# HoneyCar.net
KiCad netlist of a schematic drawn in EAGLE
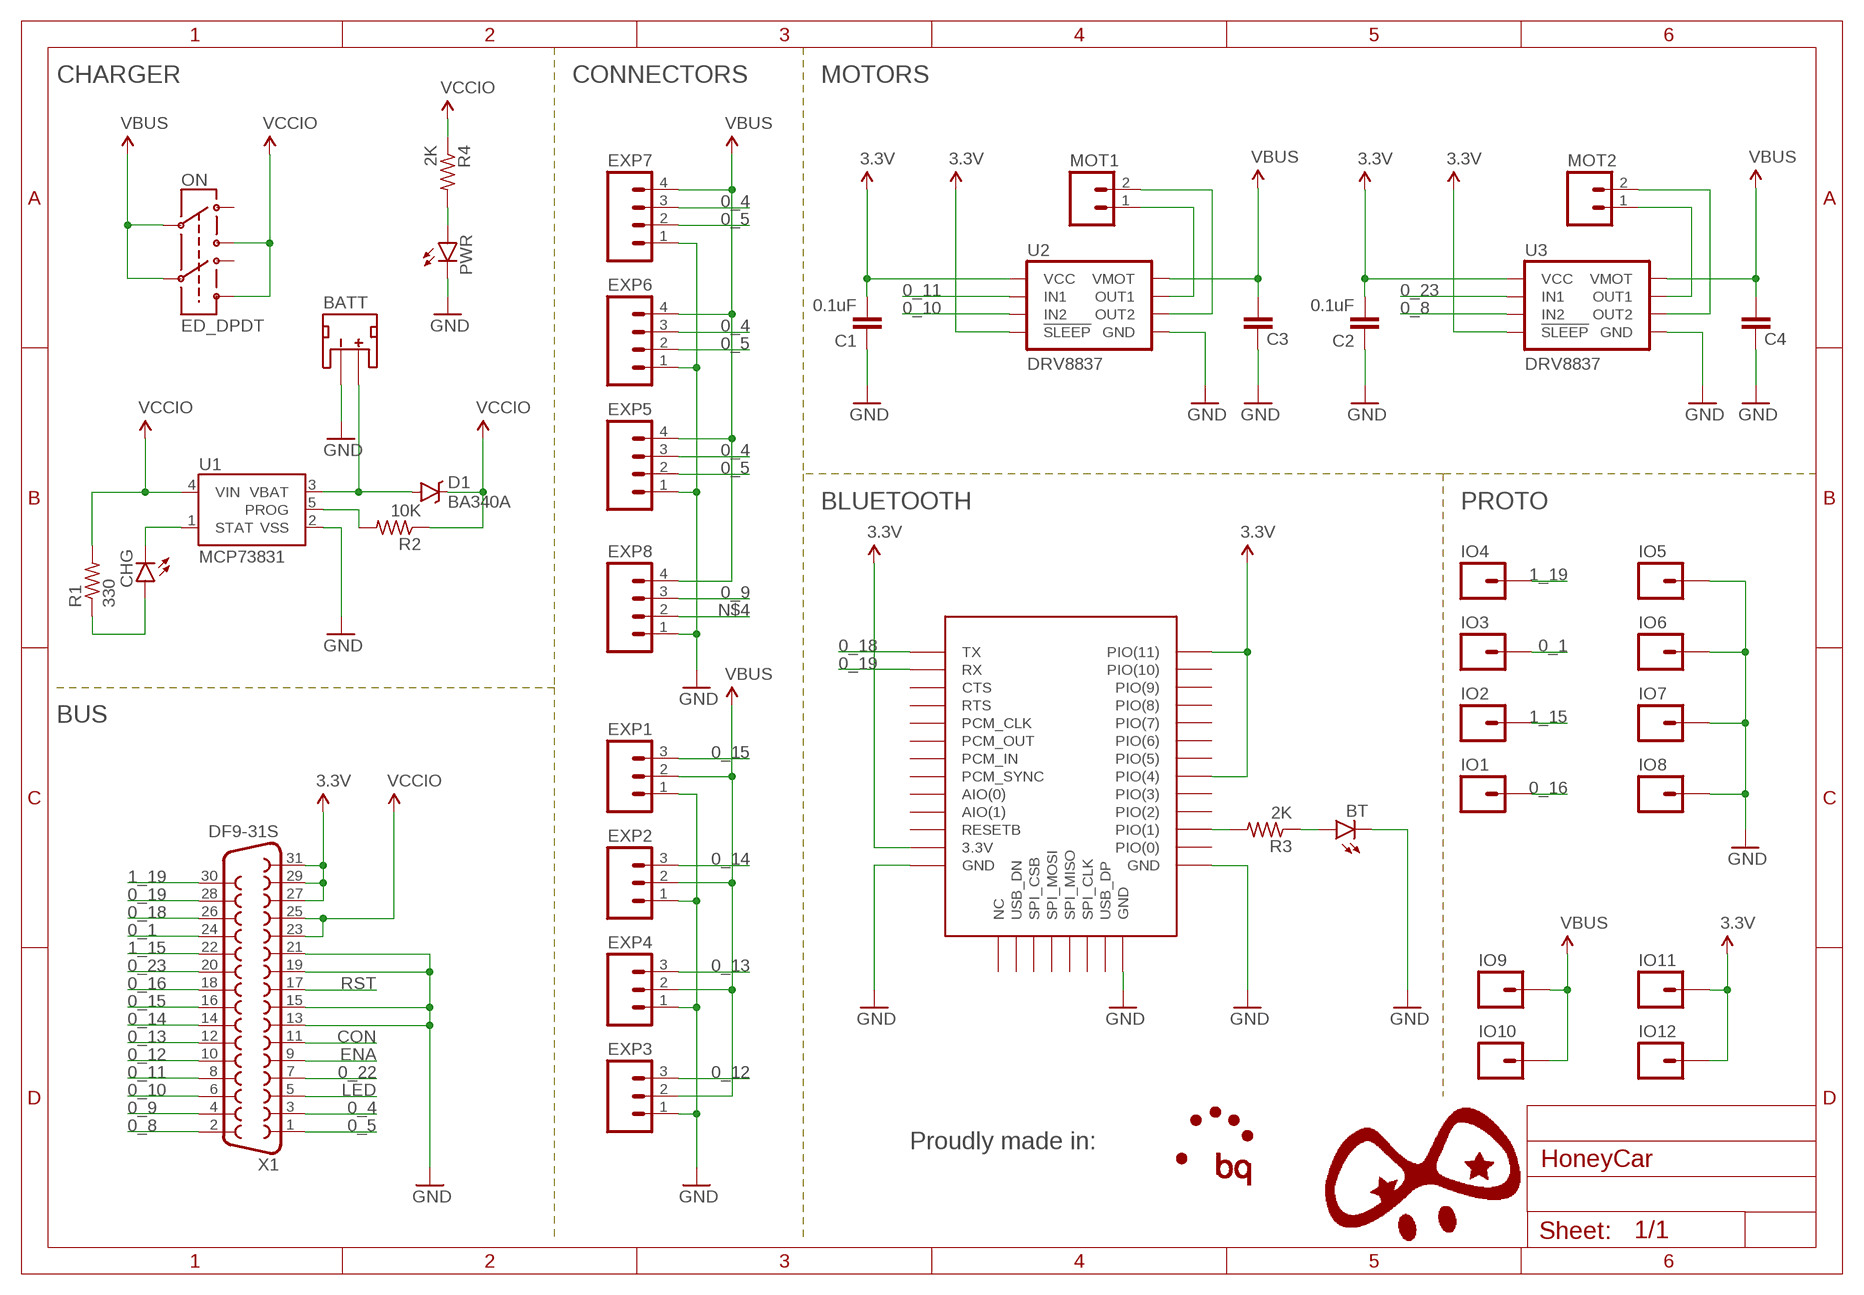
[diagram p0: schematic, sheet 1]

(export (version "E")
  (design (tool "Eeschema 10.0.6"))
  (components
    (comp (ref "BATT")
      (value "JST_2MM_MALE")
      (footprint "eagle-import:JST-2-SMD")
      (libsource (lib "eagle-import") (part "JST_2MM_MALE"))
    )
    (comp (ref "BT")
      (value "LED0603")
      (footprint "eagle-import:LED-0603")
      (libsource (lib "eagle-import") (part "LED0603"))
    )
    (comp (ref "C1")
      (value "0.1uF")
      (footprint "eagle-import:0603-CAP")
      (libsource (lib "eagle-import") (part "CAP0603-CAP"))
    )
    (comp (ref "C2")
      (value "0.1uF")
      (footprint "eagle-import:0603-CAP")
      (libsource (lib "eagle-import") (part "CAP0603-CAP"))
    )
    (comp (ref "C3")
      (value "0.1uF")
      (footprint "eagle-import:0603-CAP")
      (libsource (lib "eagle-import") (part "CAP0603-CAP"))
    )
    (comp (ref "C4")
      (value "0.1uF")
      (footprint "eagle-import:0603-CAP")
      (libsource (lib "eagle-import") (part "CAP0603-CAP"))
    )
    (comp (ref "CHG")
      (value "LED0603")
      (footprint "eagle-import:LED-0603")
      (libsource (lib "eagle-import") (part "LED0603"))
    )
    (comp (ref "D1")
      (value "BA340A")
      (footprint "eagle-import:SMA-DIODE")
      (libsource (lib "eagle-import") (part "B340A"))
    )
    (comp (ref "EXP1")
      (value "M03LOCK")
      (footprint "eagle-import:1X03_LOCK")
      (libsource (lib "eagle-import") (part "M03LOCK"))
    )
    (comp (ref "EXP2")
      (value "M03LOCK")
      (footprint "eagle-import:1X03_LOCK")
      (libsource (lib "eagle-import") (part "M03LOCK"))
    )
    (comp (ref "EXP3")
      (value "M03LOCK")
      (footprint "eagle-import:1X03_LOCK")
      (libsource (lib "eagle-import") (part "M03LOCK"))
    )
    (comp (ref "EXP4")
      (value "M03LOCK")
      (footprint "eagle-import:1X03_LOCK")
      (libsource (lib "eagle-import") (part "M03LOCK"))
    )
    (comp (ref "EXP5")
      (value "M04JST")
      (footprint "eagle-import:1X04-1.5MM_JST")
      (libsource (lib "eagle-import") (part "M04JST"))
    )
    (comp (ref "EXP6")
      (value "M04JST")
      (footprint "eagle-import:1X04-1.5MM_JST")
      (libsource (lib "eagle-import") (part "M04JST"))
    )
    (comp (ref "EXP7")
      (value "M04JST")
      (footprint "eagle-import:1X04-1.5MM_JST")
      (libsource (lib "eagle-import") (part "M04JST"))
    )
    (comp (ref "EXP8")
      (value "M04JST")
      (footprint "eagle-import:1X04-1.5MM_JST")
      (libsource (lib "eagle-import") (part "M04JST"))
    )
    (comp (ref "IC1")
      (value "BC04_BLUETOOTH")
      (footprint "eagle-import:BC04")
      (libsource (lib "eagle-import") (part "BC04_BLUETOOTH"))
    )
    (comp (ref "IO1")
      (value "M01PTH_LONGPAD")
      (footprint "eagle-import:1X01_LONGPAD")
      (libsource (lib "eagle-import") (part "M01PTH_LONGPAD"))
    )
    (comp (ref "IO2")
      (value "M01PTH_LONGPAD")
      (footprint "eagle-import:1X01_LONGPAD")
      (libsource (lib "eagle-import") (part "M01PTH_LONGPAD"))
    )
    (comp (ref "IO3")
      (value "M01PTH_LONGPAD")
      (footprint "eagle-import:1X01_LONGPAD")
      (libsource (lib "eagle-import") (part "M01PTH_LONGPAD"))
    )
    (comp (ref "IO4")
      (value "M01PTH_LONGPAD")
      (footprint "eagle-import:1X01_LONGPAD")
      (libsource (lib "eagle-import") (part "M01PTH_LONGPAD"))
    )
    (comp (ref "IO5")
      (value "M01PTH_LONGPAD")
      (footprint "eagle-import:1X01_LONGPAD")
      (libsource (lib "eagle-import") (part "M01PTH_LONGPAD"))
    )
    (comp (ref "IO6")
      (value "M01PTH_LONGPAD")
      (footprint "eagle-import:1X01_LONGPAD")
      (libsource (lib "eagle-import") (part "M01PTH_LONGPAD"))
    )
    (comp (ref "IO7")
      (value "M01PTH_LONGPAD")
      (footprint "eagle-import:1X01_LONGPAD")
      (libsource (lib "eagle-import") (part "M01PTH_LONGPAD"))
    )
    (comp (ref "IO8")
      (value "M01PTH_LONGPAD")
      (footprint "eagle-import:1X01_LONGPAD")
      (libsource (lib "eagle-import") (part "M01PTH_LONGPAD"))
    )
    (comp (ref "IO9")
      (value "M01PTH_LONGPAD")
      (footprint "eagle-import:1X01_LONGPAD")
      (libsource (lib "eagle-import") (part "M01PTH_LONGPAD"))
    )
    (comp (ref "IO10")
      (value "M01PTH_LONGPAD")
      (footprint "eagle-import:1X01_LONGPAD")
      (libsource (lib "eagle-import") (part "M01PTH_LONGPAD"))
    )
    (comp (ref "IO11")
      (value "M01PTH_LONGPAD")
      (footprint "eagle-import:1X01_LONGPAD")
      (libsource (lib "eagle-import") (part "M01PTH_LONGPAD"))
    )
    (comp (ref "IO12")
      (value "M01PTH_LONGPAD")
      (footprint "eagle-import:1X01_LONGPAD")
      (libsource (lib "eagle-import") (part "M01PTH_LONGPAD"))
    )
    (comp (ref "MOT1")
      (value "M02POLAR")
      (footprint "eagle-import:MOLEX-1X2")
      (libsource (lib "eagle-import") (part "M02POLAR"))
    )
    (comp (ref "MOT2")
      (value "M02POLAR")
      (footprint "eagle-import:MOLEX-1X2")
      (libsource (lib "eagle-import") (part "M02POLAR"))
    )
    (comp (ref "ON")
      (value "ED_DPDT")
      (footprint "eagle-import:ED_DPDT")
      (libsource (lib "eagle-import") (part "ED_DPDT"))
    )
    (comp (ref "PWR")
      (value "LED0603")
      (footprint "eagle-import:LED-0603")
      (libsource (lib "eagle-import") (part "LED0603"))
    )
    (comp (ref "R1")
      (value "330")
      (footprint "eagle-import:R0402")
      (libsource (lib "eagle-import") (part "R-US_R0402"))
    )
    (comp (ref "R2")
      (value "10K")
      (footprint "eagle-import:R0402")
      (libsource (lib "eagle-import") (part "R-US_R0402"))
    )
    (comp (ref "R3")
      (value "2K")
      (footprint "eagle-import:R0402")
      (libsource (lib "eagle-import") (part "R-US_R0402"))
    )
    (comp (ref "R4")
      (value "2K")
      (footprint "eagle-import:R0402")
      (libsource (lib "eagle-import") (part "R-US_R0402"))
    )
    (comp (ref "U1")
      (value "MCP73831")
      (footprint "eagle-import:SOT23-5")
      (libsource (lib "eagle-import") (part "MCP73831"))
    )
    (comp (ref "U2")
      (value "DRV8837")
      (footprint "eagle-import:DSG")
      (libsource (lib "eagle-import") (part "DRV8837"))
    )
    (comp (ref "U3")
      (value "DRV8837")
      (footprint "eagle-import:DSG")
      (libsource (lib "eagle-import") (part "DRV8837"))
    )
    (comp (ref "X1")
      (value "DF9-31S")
      (footprint "eagle-import:DF9-31S")
      (fields (field (name "MPN") "DF9-31S-1V(32)"))
      (libsource (lib "eagle-import") (part "DF9-31S"))
    )
  )
  (nets
    (net (code "1") (name "/0_1") (class "Default")
      (node (ref "IO3") (pin "1") (pinfunction "1_1") (pintype "passive"))
      (node (ref "X1") (pin "24") (pinfunction "24_24") (pintype "passive"))
    )
    (net (code "2") (name "/0_4") (class "Default")
      (node (ref "EXP5") (pin "3") (pinfunction "3_3") (pintype "passive"))
      (node (ref "EXP6") (pin "3") (pinfunction "3_3") (pintype "passive"))
      (node (ref "EXP7") (pin "3") (pinfunction "3_3") (pintype "passive"))
      (node (ref "X1") (pin "3") (pinfunction "3_3") (pintype "passive"))
    )
    (net (code "3") (name "/0_5") (class "Default")
      (node (ref "EXP5") (pin "2") (pinfunction "2_2") (pintype "passive"))
      (node (ref "EXP6") (pin "2") (pinfunction "2_2") (pintype "passive"))
      (node (ref "EXP7") (pin "2") (pinfunction "2_2") (pintype "passive"))
      (node (ref "X1") (pin "1") (pinfunction "1_1") (pintype "passive"))
    )
    (net (code "4") (name "/0_8") (class "Default")
      (node (ref "U3") (pin "5") (pinfunction "IN2_5") (pintype "bidirectional"))
      (node (ref "X1") (pin "2") (pinfunction "2_2") (pintype "passive"))
    )
    (net (code "5") (name "/0_9") (class "Default")
      (node (ref "EXP8") (pin "3") (pinfunction "3_3") (pintype "passive"))
      (node (ref "X1") (pin "4") (pinfunction "4_4") (pintype "passive"))
    )
    (net (code "6") (name "/0_10") (class "Default")
      (node (ref "U2") (pin "5") (pinfunction "IN2_5") (pintype "bidirectional"))
      (node (ref "X1") (pin "6") (pinfunction "6_6") (pintype "passive"))
    )
    (net (code "7") (name "/0_11") (class "Default")
      (node (ref "U2") (pin "6") (pinfunction "IN1_6") (pintype "bidirectional"))
      (node (ref "X1") (pin "8") (pinfunction "8_8") (pintype "passive"))
    )
    (net (code "8") (name "/0_12") (class "Default")
      (node (ref "EXP3") (pin "3") (pinfunction "3_3") (pintype "passive"))
      (node (ref "X1") (pin "10") (pinfunction "10_10") (pintype "passive"))
    )
    (net (code "9") (name "/0_13") (class "Default")
      (node (ref "EXP4") (pin "3") (pinfunction "3_3") (pintype "passive"))
      (node (ref "X1") (pin "12") (pinfunction "12_12") (pintype "passive"))
    )
    (net (code "10") (name "/0_14") (class "Default")
      (node (ref "EXP2") (pin "3") (pinfunction "3_3") (pintype "passive"))
      (node (ref "X1") (pin "14") (pinfunction "14_14") (pintype "passive"))
    )
    (net (code "11") (name "/0_15") (class "Default")
      (node (ref "EXP1") (pin "3") (pinfunction "3_3") (pintype "passive"))
      (node (ref "X1") (pin "16") (pinfunction "16_16") (pintype "passive"))
    )
    (net (code "12") (name "/0_16") (class "Default")
      (node (ref "IO1") (pin "1") (pinfunction "1_1") (pintype "passive"))
      (node (ref "X1") (pin "18") (pinfunction "18_18") (pintype "passive"))
    )
    (net (code "13") (name "/0_18") (class "Default")
      (node (ref "IC1") (pin "P$1") (pinfunction "TX_P$1") (pintype "bidirectional"))
      (node (ref "X1") (pin "26") (pinfunction "26_26") (pintype "passive"))
    )
    (net (code "14") (name "/0_19") (class "Default")
      (node (ref "IC1") (pin "P$2") (pinfunction "RX_P$2") (pintype "bidirectional"))
      (node (ref "X1") (pin "28") (pinfunction "28_28") (pintype "passive"))
    )
    (net (code "15") (name "/0_22") (class "Default")
      (node (ref "X1") (pin "7") (pinfunction "7_7") (pintype "passive"))
    )
    (net (code "16") (name "/0_23") (class "Default")
      (node (ref "U3") (pin "6") (pinfunction "IN1_6") (pintype "bidirectional"))
      (node (ref "X1") (pin "20") (pinfunction "20_20") (pintype "passive"))
    )
    (net (code "17") (name "/1_15") (class "Default")
      (node (ref "IO2") (pin "1") (pinfunction "1_1") (pintype "passive"))
      (node (ref "X1") (pin "22") (pinfunction "22_22") (pintype "passive"))
    )
    (net (code "18") (name "/1_19") (class "Default")
      (node (ref "IO4") (pin "1") (pinfunction "1_1") (pintype "passive"))
      (node (ref "X1") (pin "30") (pinfunction "30_30") (pintype "passive"))
    )
    (net (code "19") (name "/CON") (class "Default")
      (node (ref "X1") (pin "11") (pinfunction "11_11") (pintype "passive"))
    )
    (net (code "20") (name "/ENA") (class "Default")
      (node (ref "X1") (pin "9") (pinfunction "9_9") (pintype "passive"))
    )
    (net (code "21") (name "/LED") (class "Default")
      (node (ref "X1") (pin "5") (pinfunction "5_5") (pintype "passive"))
    )
    (net (code "22") (name "/N$4") (class "Default")
      (node (ref "EXP8") (pin "2") (pinfunction "2_2") (pintype "passive"))
    )
    (net (code "23") (name "/RST") (class "Default")
      (node (ref "X1") (pin "17") (pinfunction "17_17") (pintype "passive"))
    )
    (net (code "24") (name "3.3V") (class "Default")
      (node (ref "C1") (pin "2") (pinfunction "2_2") (pintype "passive"))
      (node (ref "C2") (pin "2") (pinfunction "2_2") (pintype "passive"))
      (node (ref "IC1") (pin "P$12") (pinfunction "3.3V_P$12") (pintype "bidirectional"))
      (node (ref "IC1") (pin "P$27") (pinfunction "PIO(4)_P$27") (pintype "bidirectional"))
      (node (ref "IC1") (pin "P$34") (pinfunction "PIO(11)_P$34") (pintype "bidirectional"))
      (node (ref "IO11") (pin "1") (pinfunction "1_1") (pintype "passive"))
      (node (ref "IO12") (pin "1") (pinfunction "1_1") (pintype "passive"))
      (node (ref "U2") (pin "7") (pinfunction "~{SLEEP}_7") (pintype "bidirectional"))
      (node (ref "U2") (pin "8") (pinfunction "VCC_8") (pintype "bidirectional"))
      (node (ref "U3") (pin "7") (pinfunction "~{SLEEP}_7") (pintype "bidirectional"))
      (node (ref "U3") (pin "8") (pinfunction "VCC_8") (pintype "bidirectional"))
      (node (ref "X1") (pin "27") (pinfunction "27_27") (pintype "passive"))
      (node (ref "X1") (pin "29") (pinfunction "29_29") (pintype "passive"))
      (node (ref "X1") (pin "31") (pinfunction "31_31") (pintype "passive"))
    )
    (net (code "25") (name "GND") (class "Default")
      (node (ref "BATT") (pin "1") (pinfunction "-_1") (pintype "bidirectional"))
      (node (ref "BT") (pin "C") (pinfunction "C_C") (pintype "passive"))
      (node (ref "C1") (pin "1") (pinfunction "1_1") (pintype "passive"))
      (node (ref "C2") (pin "1") (pinfunction "1_1") (pintype "passive"))
      (node (ref "C3") (pin "1") (pinfunction "1_1") (pintype "passive"))
      (node (ref "C4") (pin "1") (pinfunction "1_1") (pintype "passive"))
      (node (ref "EXP1") (pin "1") (pinfunction "1_1") (pintype "passive"))
      (node (ref "EXP2") (pin "1") (pinfunction "1_1") (pintype "passive"))
      (node (ref "EXP3") (pin "1") (pinfunction "1_1") (pintype "passive"))
      (node (ref "EXP4") (pin "1") (pinfunction "1_1") (pintype "passive"))
      (node (ref "EXP5") (pin "1") (pinfunction "1_1") (pintype "passive"))
      (node (ref "EXP6") (pin "1") (pinfunction "1_1") (pintype "passive"))
      (node (ref "EXP7") (pin "1") (pinfunction "1_1") (pintype "passive"))
      (node (ref "EXP8") (pin "1") (pinfunction "1_1") (pintype "passive"))
      (node (ref "IC1") (pin "P$13") (pinfunction "GND_P$13") (pintype "bidirectional"))
      (node (ref "IC1") (pin "P$21") (pinfunction "GND_P$21") (pintype "bidirectional"))
      (node (ref "IC1") (pin "P$22") (pinfunction "GND_P$22") (pintype "bidirectional"))
      (node (ref "IO5") (pin "1") (pinfunction "1_1") (pintype "passive"))
      (node (ref "IO6") (pin "1") (pinfunction "1_1") (pintype "passive"))
      (node (ref "IO7") (pin "1") (pinfunction "1_1") (pintype "passive"))
      (node (ref "IO8") (pin "1") (pinfunction "1_1") (pintype "passive"))
      (node (ref "PWR") (pin "C") (pinfunction "C_C") (pintype "passive"))
      (node (ref "U1") (pin "2") (pinfunction "VSS_2") (pintype "power_in"))
      (node (ref "U2") (pin "4") (pinfunction "GND_4") (pintype "bidirectional"))
      (node (ref "U2") (pin "PAD") (pinfunction "GND_PAD") (pintype "bidirectional"))
      (node (ref "U3") (pin "4") (pinfunction "GND_4") (pintype "bidirectional"))
      (node (ref "U3") (pin "PAD") (pinfunction "GND_PAD") (pintype "bidirectional"))
      (node (ref "X1") (pin "13") (pinfunction "13_13") (pintype "passive"))
      (node (ref "X1") (pin "15") (pinfunction "15_15") (pintype "passive"))
      (node (ref "X1") (pin "19") (pinfunction "19_19") (pintype "passive"))
      (node (ref "X1") (pin "21") (pinfunction "21_21") (pintype "passive"))
    )
    (net (code "26") (name "Net-(BATT-+)") (class "Default")
      (node (ref "BATT") (pin "2") (pinfunction "+_2") (pintype "bidirectional"))
      (node (ref "D1") (pin "A") (pinfunction "A_A") (pintype "passive"))
      (node (ref "U1") (pin "3") (pinfunction "VBAT_3") (pintype "power_in"))
    )
    (net (code "27") (name "Net-(BT-PadA)") (class "Default")
      (node (ref "BT") (pin "A") (pinfunction "A_A") (pintype "passive"))
      (node (ref "R3") (pin "1") (pinfunction "1_1") (pintype "passive"))
    )
    (net (code "28") (name "Net-(CHG-PadA)") (class "Default")
      (node (ref "CHG") (pin "A") (pinfunction "A_A") (pintype "passive"))
      (node (ref "R1") (pin "1") (pinfunction "1_1") (pintype "passive"))
    )
    (net (code "29") (name "Net-(IC1-PIO(1))") (class "Default")
      (node (ref "IC1") (pin "P$24") (pinfunction "PIO(1)_P$24") (pintype "bidirectional"))
      (node (ref "R3") (pin "2") (pinfunction "2_2") (pintype "passive"))
    )
    (net (code "30") (name "Net-(PWR-PadA)") (class "Default")
      (node (ref "PWR") (pin "A") (pinfunction "A_A") (pintype "passive"))
      (node (ref "R4") (pin "2") (pinfunction "2_2") (pintype "passive"))
    )
    (net (code "31") (name "Net-(U1-PROG)") (class "Default")
      (node (ref "R2") (pin "2") (pinfunction "2_2") (pintype "passive"))
      (node (ref "U1") (pin "5") (pinfunction "PROG_5") (pintype "input"))
    )
    (net (code "32") (name "Net-(U1-STAT)") (class "Default")
      (node (ref "CHG") (pin "C") (pinfunction "C_C") (pintype "passive"))
      (node (ref "U1") (pin "1") (pinfunction "STAT_1") (pintype "output"))
    )
    (net (code "33") (name "Net-(U2-OUT1)") (class "Default")
      (node (ref "MOT1") (pin "1") (pinfunction "1_1") (pintype "passive"))
      (node (ref "U2") (pin "2") (pinfunction "OUT1_2") (pintype "bidirectional"))
    )
    (net (code "34") (name "Net-(U2-OUT2)") (class "Default")
      (node (ref "MOT1") (pin "2") (pinfunction "2_2") (pintype "passive"))
      (node (ref "U2") (pin "3") (pinfunction "OUT2_3") (pintype "bidirectional"))
    )
    (net (code "35") (name "Net-(U3-OUT1)") (class "Default")
      (node (ref "MOT2") (pin "1") (pinfunction "1_1") (pintype "passive"))
      (node (ref "U3") (pin "2") (pinfunction "OUT1_2") (pintype "bidirectional"))
    )
    (net (code "36") (name "Net-(U3-OUT2)") (class "Default")
      (node (ref "MOT2") (pin "2") (pinfunction "2_2") (pintype "passive"))
      (node (ref "U3") (pin "3") (pinfunction "OUT2_3") (pintype "bidirectional"))
    )
    (net (code "37") (name "VBUS") (class "Default")
      (node (ref "C3") (pin "2") (pinfunction "2_2") (pintype "passive"))
      (node (ref "C4") (pin "2") (pinfunction "2_2") (pintype "passive"))
      (node (ref "EXP1") (pin "2") (pinfunction "2_2") (pintype "passive"))
      (node (ref "EXP2") (pin "2") (pinfunction "2_2") (pintype "passive"))
      (node (ref "EXP3") (pin "2") (pinfunction "2_2") (pintype "passive"))
      (node (ref "EXP4") (pin "2") (pinfunction "2_2") (pintype "passive"))
      (node (ref "EXP5") (pin "4") (pinfunction "4_4") (pintype "passive"))
      (node (ref "EXP6") (pin "4") (pinfunction "4_4") (pintype "passive"))
      (node (ref "EXP7") (pin "4") (pinfunction "4_4") (pintype "passive"))
      (node (ref "EXP8") (pin "4") (pinfunction "4_4") (pintype "passive"))
      (node (ref "IO10") (pin "1") (pinfunction "1_1") (pintype "passive"))
      (node (ref "IO9") (pin "1") (pinfunction "1_1") (pintype "passive"))
      (node (ref "ON") (pin "2") (pinfunction "2_2") (pintype "bidirectional"))
      (node (ref "ON") (pin "5") (pinfunction "5_5") (pintype "bidirectional"))
      (node (ref "U2") (pin "1") (pinfunction "VMOT_1") (pintype "bidirectional"))
      (node (ref "U3") (pin "1") (pinfunction "VMOT_1") (pintype "bidirectional"))
    )
    (net (code "38") (name "VCCIO") (class "Default")
      (node (ref "D1") (pin "C") (pinfunction "C_C") (pintype "passive"))
      (node (ref "ON") (pin "3") (pinfunction "3_3") (pintype "bidirectional"))
      (node (ref "ON") (pin "6") (pinfunction "6_6") (pintype "bidirectional"))
      (node (ref "R1") (pin "2") (pinfunction "2_2") (pintype "passive"))
      (node (ref "R2") (pin "1") (pinfunction "1_1") (pintype "passive"))
      (node (ref "R4") (pin "1") (pinfunction "1_1") (pintype "passive"))
      (node (ref "U1") (pin "4") (pinfunction "VIN_4") (pintype "power_in"))
      (node (ref "X1") (pin "23") (pinfunction "23_23") (pintype "passive"))
      (node (ref "X1") (pin "25") (pinfunction "25_25") (pintype "passive"))
    )
    (net (code "39") (name "unconnected-(BATT-PAD1-PadNC1)") (class "Default")
      (node (ref "BATT") (pin "NC1") (pinfunction "PAD1_NC1") (pintype "bidirectional"))
    )
    (net (code "40") (name "unconnected-(BATT-PAD2-PadNC2)") (class "Default")
      (node (ref "BATT") (pin "NC2") (pinfunction "PAD2_NC2") (pintype "bidirectional"))
    )
    (net (code "41") (name "unconnected-(IC1-AIO(0)-PadP$9)") (class "Default")
      (node (ref "IC1") (pin "P$9") (pinfunction "AIO(0)_P$9") (pintype "bidirectional"))
    )
    (net (code "42") (name "unconnected-(IC1-AIO(1)-PadP$10)") (class "Default")
      (node (ref "IC1") (pin "P$10") (pinfunction "AIO(1)_P$10") (pintype "bidirectional"))
    )
    (net (code "43") (name "unconnected-(IC1-CTS-PadP$3)") (class "Default")
      (node (ref "IC1") (pin "P$3") (pinfunction "CTS_P$3") (pintype "bidirectional"))
    )
    (net (code "44") (name "unconnected-(IC1-NC-PadP$14)") (class "Default")
      (node (ref "IC1") (pin "P$14") (pinfunction "NC_P$14") (pintype "bidirectional"))
    )
    (net (code "45") (name "unconnected-(IC1-PCM_CLK-PadP$5)") (class "Default")
      (node (ref "IC1") (pin "P$5") (pinfunction "PCM_CLK_P$5") (pintype "bidirectional"))
    )
    (net (code "46") (name "unconnected-(IC1-PCM_IN-PadP$7)") (class "Default")
      (node (ref "IC1") (pin "P$7") (pinfunction "PCM_IN_P$7") (pintype "bidirectional"))
    )
    (net (code "47") (name "unconnected-(IC1-PCM_OUT-PadP$6)") (class "Default")
      (node (ref "IC1") (pin "P$6") (pinfunction "PCM_OUT_P$6") (pintype "bidirectional"))
    )
    (net (code "48") (name "unconnected-(IC1-PCM_SYNC-PadP$8)") (class "Default")
      (node (ref "IC1") (pin "P$8") (pinfunction "PCM_SYNC_P$8") (pintype "bidirectional"))
    )
    (net (code "49") (name "unconnected-(IC1-PIO(0)-PadP$23)") (class "Default")
      (node (ref "IC1") (pin "P$23") (pinfunction "PIO(0)_P$23") (pintype "bidirectional"))
    )
    (net (code "50") (name "unconnected-(IC1-PIO(2)-PadP$25)") (class "Default")
      (node (ref "IC1") (pin "P$25") (pinfunction "PIO(2)_P$25") (pintype "bidirectional"))
    )
    (net (code "51") (name "unconnected-(IC1-PIO(3)-PadP$26)") (class "Default")
      (node (ref "IC1") (pin "P$26") (pinfunction "PIO(3)_P$26") (pintype "bidirectional"))
    )
    (net (code "52") (name "unconnected-(IC1-PIO(5)-PadP$28)") (class "Default")
      (node (ref "IC1") (pin "P$28") (pinfunction "PIO(5)_P$28") (pintype "bidirectional"))
    )
    (net (code "53") (name "unconnected-(IC1-PIO(6)-PadP$29)") (class "Default")
      (node (ref "IC1") (pin "P$29") (pinfunction "PIO(6)_P$29") (pintype "bidirectional"))
    )
    (net (code "54") (name "unconnected-(IC1-PIO(7)-PadP$30)") (class "Default")
      (node (ref "IC1") (pin "P$30") (pinfunction "PIO(7)_P$30") (pintype "bidirectional"))
    )
    (net (code "55") (name "unconnected-(IC1-PIO(8)-PadP$31)") (class "Default")
      (node (ref "IC1") (pin "P$31") (pinfunction "PIO(8)_P$31") (pintype "bidirectional"))
    )
    (net (code "56") (name "unconnected-(IC1-PIO(9)-PadP$32)") (class "Default")
      (node (ref "IC1") (pin "P$32") (pinfunction "PIO(9)_P$32") (pintype "bidirectional"))
    )
    (net (code "57") (name "unconnected-(IC1-PIO(10)-PadP$33)") (class "Default")
      (node (ref "IC1") (pin "P$33") (pinfunction "PIO(10)_P$33") (pintype "bidirectional"))
    )
    (net (code "58") (name "unconnected-(IC1-RESETB-PadP$11)") (class "Default")
      (node (ref "IC1") (pin "P$11") (pinfunction "RESETB_P$11") (pintype "bidirectional"))
    )
    (net (code "59") (name "unconnected-(IC1-RTS-PadP$4)") (class "Default")
      (node (ref "IC1") (pin "P$4") (pinfunction "RTS_P$4") (pintype "bidirectional"))
    )
    (net (code "60") (name "unconnected-(IC1-SPI_CLK-PadP$19)") (class "Default")
      (node (ref "IC1") (pin "P$19") (pinfunction "SPI_CLK_P$19") (pintype "bidirectional"))
    )
    (net (code "61") (name "unconnected-(IC1-SPI_CSB-PadP$16)") (class "Default")
      (node (ref "IC1") (pin "P$16") (pinfunction "SPI_CSB_P$16") (pintype "bidirectional"))
    )
    (net (code "62") (name "unconnected-(IC1-SPI_MISO-PadP$18)") (class "Default")
      (node (ref "IC1") (pin "P$18") (pinfunction "SPI_MISO_P$18") (pintype "bidirectional"))
    )
    (net (code "63") (name "unconnected-(IC1-SPI_MOSI-PadP$17)") (class "Default")
      (node (ref "IC1") (pin "P$17") (pinfunction "SPI_MOSI_P$17") (pintype "bidirectional"))
    )
    (net (code "64") (name "unconnected-(IC1-USB_DN-PadP$15)") (class "Default")
      (node (ref "IC1") (pin "P$15") (pinfunction "USB_DN_P$15") (pintype "bidirectional"))
    )
    (net (code "65") (name "unconnected-(IC1-USB_DP-PadP$20)") (class "Default")
      (node (ref "IC1") (pin "P$20") (pinfunction "USB_DP_P$20") (pintype "bidirectional"))
    )
    (net (code "66") (name "unconnected-(ON-Pad1)") (class "Default")
      (node (ref "ON") (pin "1") (pinfunction "1_1") (pintype "bidirectional"))
    )
    (net (code "67") (name "unconnected-(ON-Pad4)") (class "Default")
      (node (ref "ON") (pin "4") (pinfunction "4_4") (pintype "bidirectional"))
    )
  )
)
